# Sheet2.net
KiCad netlist of a schematic drawn in Altium Designer
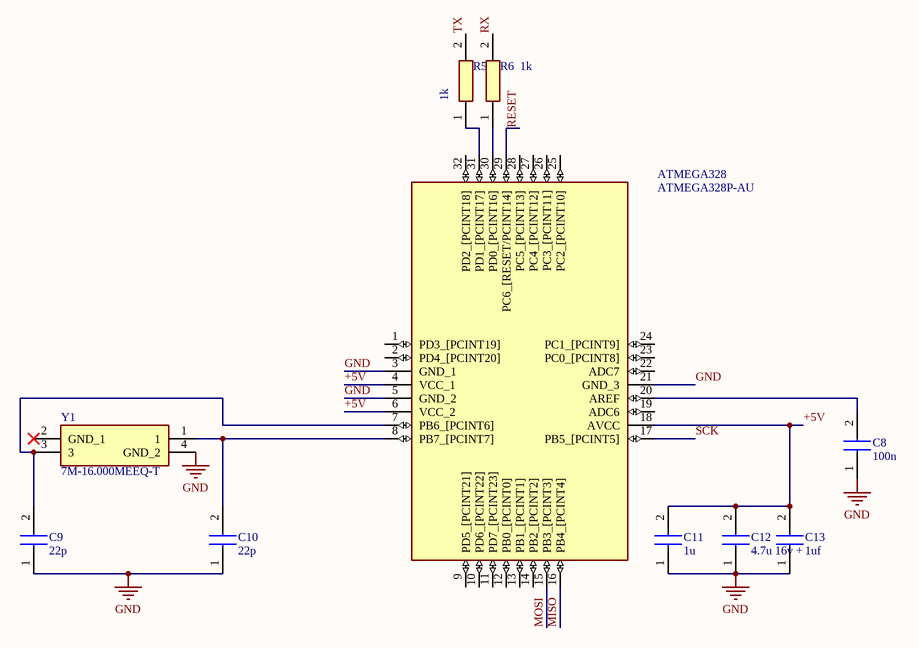
[diagram p0: Sheet2.SchDoc]

(export (version "E")
  (design (tool "Eeschema 10.0.6"))
  (components
    (comp (ref "ATMEGA328")
      (value "ATMEGA328P-AU")
      (footprint "SamacSys:QFP80P900X900X120-32N")
      (description "Integrated Circuit")
      (fields (field (name "MOUSER PART NUMBER") "556-ATMEGA328P-AU"))
      (libsource (lib "SamacSys") (part "ATMEGA328P-AU"))
    )
    (comp (ref "C8")
      (value "100n")
      (footprint "SamacSys:CAPC1608X87N")
      (description "Capacitor")
      (fields (field (name "MANUFACTURER_PART_NUMBER") "C0603C569J5GACTU"))
      (libsource (lib "SamacSys") (part "C0603C569J5GACTU"))
    )
    (comp (ref "C9")
      (value "22p")
      (footprint "SamacSys:CAPC1608X87N")
      (description "Capacitor")
      (fields (field (name "MANUFACTURER_PART_NUMBER") "C0603C569J5GACTU"))
      (libsource (lib "SamacSys") (part "C0603C569J5GACTU"))
    )
    (comp (ref "C10")
      (value "22p")
      (footprint "SamacSys:CAPC1608X87N")
      (description "Capacitor")
      (fields (field (name "MANUFACTURER_PART_NUMBER") "C0603C569J5GACTU"))
      (libsource (lib "SamacSys") (part "C0603C569J5GACTU"))
    )
    (comp (ref "C11")
      (value "1u")
      (footprint "SamacSys:CAPC1608X87N")
      (description "Capacitor")
      (fields (field (name "MANUFACTURER_PART_NUMBER") "C0603C569J5GACTU"))
      (libsource (lib "SamacSys") (part "C0603C569J5GACTU"))
    )
    (comp (ref "C12")
      (value "4.7u 16v +")
      (footprint "SamacSys:CAPC1608X87N")
      (description "Capacitor")
      (fields (field (name "MANUFACTURER_PART_NUMBER") "C0603C569J5GACTU"))
      (libsource (lib "SamacSys") (part "C0603C569J5GACTU"))
    )
    (comp (ref "C13")
      (value "1uf")
      (footprint "SamacSys:CAPC1608X87N")
      (description "Capacitor")
      (fields (field (name "MANUFACTURER_PART_NUMBER") "C0603C569J5GACTU"))
      (libsource (lib "SamacSys") (part "C0603C569J5GACTU"))
    )
    (comp (ref "R5")
      (value "1k")
      (footprint "SamacSys:RESC2012X65N")
      (description "Resistor")
      (fields (field (name "MANUFACTURER_PART_NUMBER") "CPF0805B340RE1"))
      (libsource (lib "SamacSys") (part "CPF0805B340RE1"))
    )
    (comp (ref "R6")
      (value "1k")
      (footprint "SamacSys:RESC2012X65N")
      (description "Resistor")
      (fields (field (name "MANUFACTURER_PART_NUMBER") "CPF0805B340RE1"))
      (libsource (lib "SamacSys") (part "CPF0805B340RE1"))
    )
    (comp (ref "Y1")
      (value "7M-16.000MEEQ-T")
      (footprint "SamacSys:7M")
      (description "Crystals 16.000MHz 10ppm -20 +70C 10pF")
      (fields (field (name "MOUSER PART NUMBER") "717-7M-16.000MEEQ-T"))
      (libsource (lib "SamacSys") (part "7M-16.000MEEQ-T"))
    )
  )
  (nets
    (net (code "1") (name "/+5V") (class "Default")
      (node (ref "ATMEGA328") (pin "18") (pinfunction "AVCC_18") (pintype "power_in"))
      (node (ref "ATMEGA328") (pin "4") (pinfunction "VCC_1_4") (pintype "power_in"))
      (node (ref "ATMEGA328") (pin "6") (pinfunction "VCC_2_6") (pintype "power_in"))
      (node (ref "C11") (pin "2") (pinfunction "2_2") (pintype "passive"))
      (node (ref "C12") (pin "2") (pinfunction "2_2") (pintype "passive"))
      (node (ref "C13") (pin "2") (pinfunction "2_2") (pintype "passive"))
    )
    (net (code "2") (name "/MISO") (class "Default")
      (node (ref "ATMEGA328") (pin "16") (pinfunction "PB4_[PCINT4]_16") (pintype "bidirectional"))
    )
    (net (code "3") (name "/MOSI") (class "Default")
      (node (ref "ATMEGA328") (pin "15") (pinfunction "PB3_[PCINT3]_15") (pintype "bidirectional"))
    )
    (net (code "4") (name "/RESET") (class "Default")
      (node (ref "ATMEGA328") (pin "29") (pinfunction "PC6_[RESET/PCINT14]_29") (pintype "bidirectional"))
    )
    (net (code "5") (name "/RX") (class "Default")
      (node (ref "R6") (pin "2") (pinfunction "2_2") (pintype "passive"))
    )
    (net (code "6") (name "/SCK") (class "Default")
      (node (ref "ATMEGA328") (pin "17") (pinfunction "PB5_[PCINT5]_17") (pintype "bidirectional"))
    )
    (net (code "7") (name "/TX") (class "Default")
      (node (ref "R5") (pin "2") (pinfunction "2_2") (pintype "passive"))
    )
    (net (code "8") (name "GND") (class "Default")
      (node (ref "ATMEGA328") (pin "21") (pinfunction "GND_3_21") (pintype "power_in"))
      (node (ref "ATMEGA328") (pin "3") (pinfunction "GND_1_3") (pintype "power_in"))
      (node (ref "ATMEGA328") (pin "5") (pinfunction "GND_2_5") (pintype "power_in"))
      (node (ref "C10") (pin "1") (pinfunction "1_1") (pintype "passive"))
      (node (ref "C11") (pin "1") (pinfunction "1_1") (pintype "passive"))
      (node (ref "C12") (pin "1") (pinfunction "1_1") (pintype "passive"))
      (node (ref "C13") (pin "1") (pinfunction "1_1") (pintype "passive"))
      (node (ref "C8") (pin "1") (pinfunction "1_1") (pintype "passive"))
      (node (ref "C9") (pin "1") (pinfunction "1_1") (pintype "passive"))
      (node (ref "Y1") (pin "4") (pinfunction "GND_2_4") (pintype "passive"))
    )
    (net (code "9") (name "Net-(ATMEGA328-AREF)") (class "Default")
      (node (ref "ATMEGA328") (pin "20") (pinfunction "AREF_20") (pintype "bidirectional"))
      (node (ref "C8") (pin "2") (pinfunction "2_2") (pintype "passive"))
    )
    (net (code "10") (name "Net-(ATMEGA328-PB6_[PCINT6])") (class "Default")
      (node (ref "ATMEGA328") (pin "7") (pinfunction "PB6_[PCINT6]_7") (pintype "bidirectional"))
      (node (ref "C9") (pin "2") (pinfunction "2_2") (pintype "passive"))
      (node (ref "Y1") (pin "3") (pinfunction "3_3") (pintype "passive"))
    )
    (net (code "11") (name "Net-(ATMEGA328-PB7_[PCINT7])") (class "Default")
      (node (ref "ATMEGA328") (pin "8") (pinfunction "PB7_[PCINT7]_8") (pintype "bidirectional"))
      (node (ref "C10") (pin "2") (pinfunction "2_2") (pintype "passive"))
      (node (ref "Y1") (pin "1") (pinfunction "1_1") (pintype "passive"))
    )
    (net (code "12") (name "Net-(ATMEGA328-PD0_[PCINT16])") (class "Default")
      (node (ref "ATMEGA328") (pin "30") (pinfunction "PD0_[PCINT16]_30") (pintype "bidirectional"))
      (node (ref "R6") (pin "1") (pinfunction "1_1") (pintype "passive"))
    )
    (net (code "13") (name "Net-(ATMEGA328-PD1_[PCINT17])") (class "Default")
      (node (ref "ATMEGA328") (pin "31") (pinfunction "PD1_[PCINT17]_31") (pintype "bidirectional"))
      (node (ref "R5") (pin "1") (pinfunction "1_1") (pintype "passive"))
    )
    (net (code "14") (name "unconnected-(ATMEGA328-ADC6-Pad19)") (class "Default")
      (node (ref "ATMEGA328") (pin "19") (pinfunction "ADC6_19") (pintype "bidirectional"))
    )
    (net (code "15") (name "unconnected-(ATMEGA328-ADC7-Pad22)") (class "Default")
      (node (ref "ATMEGA328") (pin "22") (pinfunction "ADC7_22") (pintype "bidirectional"))
    )
    (net (code "16") (name "unconnected-(ATMEGA328-PB0_[PCINT0]-Pad12)") (class "Default")
      (node (ref "ATMEGA328") (pin "12") (pinfunction "PB0_[PCINT0]_12") (pintype "bidirectional"))
    )
    (net (code "17") (name "unconnected-(ATMEGA328-PB1_[PCINT1]-Pad13)") (class "Default")
      (node (ref "ATMEGA328") (pin "13") (pinfunction "PB1_[PCINT1]_13") (pintype "bidirectional"))
    )
    (net (code "18") (name "unconnected-(ATMEGA328-PB2_[PCINT2]-Pad14)") (class "Default")
      (node (ref "ATMEGA328") (pin "14") (pinfunction "PB2_[PCINT2]_14") (pintype "bidirectional"))
    )
    (net (code "19") (name "unconnected-(ATMEGA328-PC0_[PCINT8]-Pad23)") (class "Default")
      (node (ref "ATMEGA328") (pin "23") (pinfunction "PC0_[PCINT8]_23") (pintype "bidirectional"))
    )
    (net (code "20") (name "unconnected-(ATMEGA328-PC1_[PCINT9]-Pad24)") (class "Default")
      (node (ref "ATMEGA328") (pin "24") (pinfunction "PC1_[PCINT9]_24") (pintype "bidirectional"))
    )
    (net (code "21") (name "unconnected-(ATMEGA328-PC2_[PCINT10]-Pad25)") (class "Default")
      (node (ref "ATMEGA328") (pin "25") (pinfunction "PC2_[PCINT10]_25") (pintype "bidirectional"))
    )
    (net (code "22") (name "unconnected-(ATMEGA328-PC3_[PCINT11]-Pad26)") (class "Default")
      (node (ref "ATMEGA328") (pin "26") (pinfunction "PC3_[PCINT11]_26") (pintype "bidirectional"))
    )
    (net (code "23") (name "unconnected-(ATMEGA328-PC4_[PCINT12]-Pad27)") (class "Default")
      (node (ref "ATMEGA328") (pin "27") (pinfunction "PC4_[PCINT12]_27") (pintype "bidirectional"))
    )
    (net (code "24") (name "unconnected-(ATMEGA328-PC5_[PCINT13]-Pad28)") (class "Default")
      (node (ref "ATMEGA328") (pin "28") (pinfunction "PC5_[PCINT13]_28") (pintype "bidirectional"))
    )
    (net (code "25") (name "unconnected-(ATMEGA328-PD2_[PCINT18]-Pad32)") (class "Default")
      (node (ref "ATMEGA328") (pin "32") (pinfunction "PD2_[PCINT18]_32") (pintype "bidirectional"))
    )
    (net (code "26") (name "unconnected-(ATMEGA328-PD3_[PCINT19]-Pad1)") (class "Default")
      (node (ref "ATMEGA328") (pin "1") (pinfunction "PD3_[PCINT19]_1") (pintype "bidirectional"))
    )
    (net (code "27") (name "unconnected-(ATMEGA328-PD4_[PCINT20]-Pad2)") (class "Default")
      (node (ref "ATMEGA328") (pin "2") (pinfunction "PD4_[PCINT20]_2") (pintype "bidirectional"))
    )
    (net (code "28") (name "unconnected-(ATMEGA328-PD5_[PCINT21]-Pad9)") (class "Default")
      (node (ref "ATMEGA328") (pin "9") (pinfunction "PD5_[PCINT21]_9") (pintype "bidirectional"))
    )
    (net (code "29") (name "unconnected-(ATMEGA328-PD6_[PCINT22]-Pad10)") (class "Default")
      (node (ref "ATMEGA328") (pin "10") (pinfunction "PD6_[PCINT22]_10") (pintype "bidirectional"))
    )
    (net (code "30") (name "unconnected-(ATMEGA328-PD7_[PCINT23]-Pad11)") (class "Default")
      (node (ref "ATMEGA328") (pin "11") (pinfunction "PD7_[PCINT23]_11") (pintype "bidirectional"))
    )
    (net (code "31") (name "unconnected-(Y1-GND_1-Pad2)") (class "Default")
      (node (ref "Y1") (pin "2") (pinfunction "GND_1_2") (pintype "passive+no_connect"))
    )
  )
)
